# ShineSensor.net
KiCad netlist of a schematic drawn in EAGLE
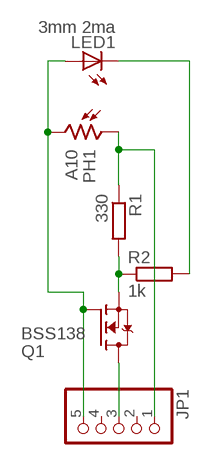
[diagram p0: schematic, sheet 1]

(export (version "E")
  (design (tool "Eeschema 10.0.6"))
  (components
    (comp (ref "JP1")
      (value "PINHD-1X5")
      (footprint "eagle-import:1X05")
      (libsource (lib "eagle-import") (part "PINHD-1X5"))
    )
    (comp (ref "LED1")
      (value "3mm 2ma")
      (footprint "eagle-import:LED3MM")
      (fields (field (name "MF") "VISHAY SEMICONDUCTOR"))
      (libsource (lib "eagle-import") (part "TLLY4400"))
    )
    (comp (ref "PH1")
      (value "A10")
      (footprint "eagle-import:T0-46-A10XX")
      (libsource (lib "eagle-import") (part "A1050_11"))
    )
    (comp (ref "Q1")
      (value "BSS138")
      (footprint "eagle-import:SOT23")
      (fields (field (name "MF") "Fairchild"))
      (libsource (lib "eagle-import") (part "BSS138"))
    )
    (comp (ref "R1")
      (value "330")
      (footprint "eagle-import:R1206")
      (libsource (lib "eagle-import") (part "R-EU_R1206"))
    )
    (comp (ref "R2")
      (value "1k")
      (footprint "eagle-import:R1206")
      (libsource (lib "eagle-import") (part "R-EU_R1206"))
    )
  )
  (nets
    (net (code "1") (name "Net-(JP1-Pad1)") (class "Default")
      (node (ref "JP1") (pin "1") (pinfunction "1_1") (pintype "passive"))
      (node (ref "PH1") (pin "1") (pinfunction "1_1") (pintype "passive"))
      (node (ref "R1") (pin "1") (pinfunction "1_1") (pintype "passive"))
    )
    (net (code "2") (name "Net-(LED1-C)") (class "Default")
      (node (ref "LED1") (pin "K") (pinfunction "C_K") (pintype "passive"))
      (node (ref "R2") (pin "2") (pinfunction "2_2") (pintype "passive"))
    )
    (net (code "3") (name "Net-(Q1-D)") (class "Default")
      (node (ref "JP1") (pin "3") (pinfunction "3_3") (pintype "passive"))
      (node (ref "Q1") (pin "3") (pinfunction "D_3") (pintype "passive"))
    )
    (net (code "4") (name "Net-(Q1-G)") (class "Default")
      (node (ref "JP1") (pin "5") (pinfunction "5_5") (pintype "passive"))
      (node (ref "LED1") (pin "A") (pinfunction "A_A") (pintype "passive"))
      (node (ref "PH1") (pin "2") (pinfunction "2_2") (pintype "passive"))
      (node (ref "Q1") (pin "1") (pinfunction "G_1") (pintype "passive"))
    )
    (net (code "5") (name "Net-(Q1-S)") (class "Default")
      (node (ref "Q1") (pin "2") (pinfunction "S_2") (pintype "passive"))
      (node (ref "R1") (pin "2") (pinfunction "2_2") (pintype "passive"))
      (node (ref "R2") (pin "1") (pinfunction "1_1") (pintype "passive"))
    )
    (net (code "6") (name "unconnected-(JP1-Pad2)") (class "Default")
      (node (ref "JP1") (pin "2") (pinfunction "2_2") (pintype "passive"))
    )
    (net (code "7") (name "unconnected-(JP1-Pad4)") (class "Default")
      (node (ref "JP1") (pin "4") (pinfunction "4_4") (pintype "passive"))
    )
  )
)
